# 06_-_POWER.net
KiCad netlist of a schematic drawn in Altium Designer
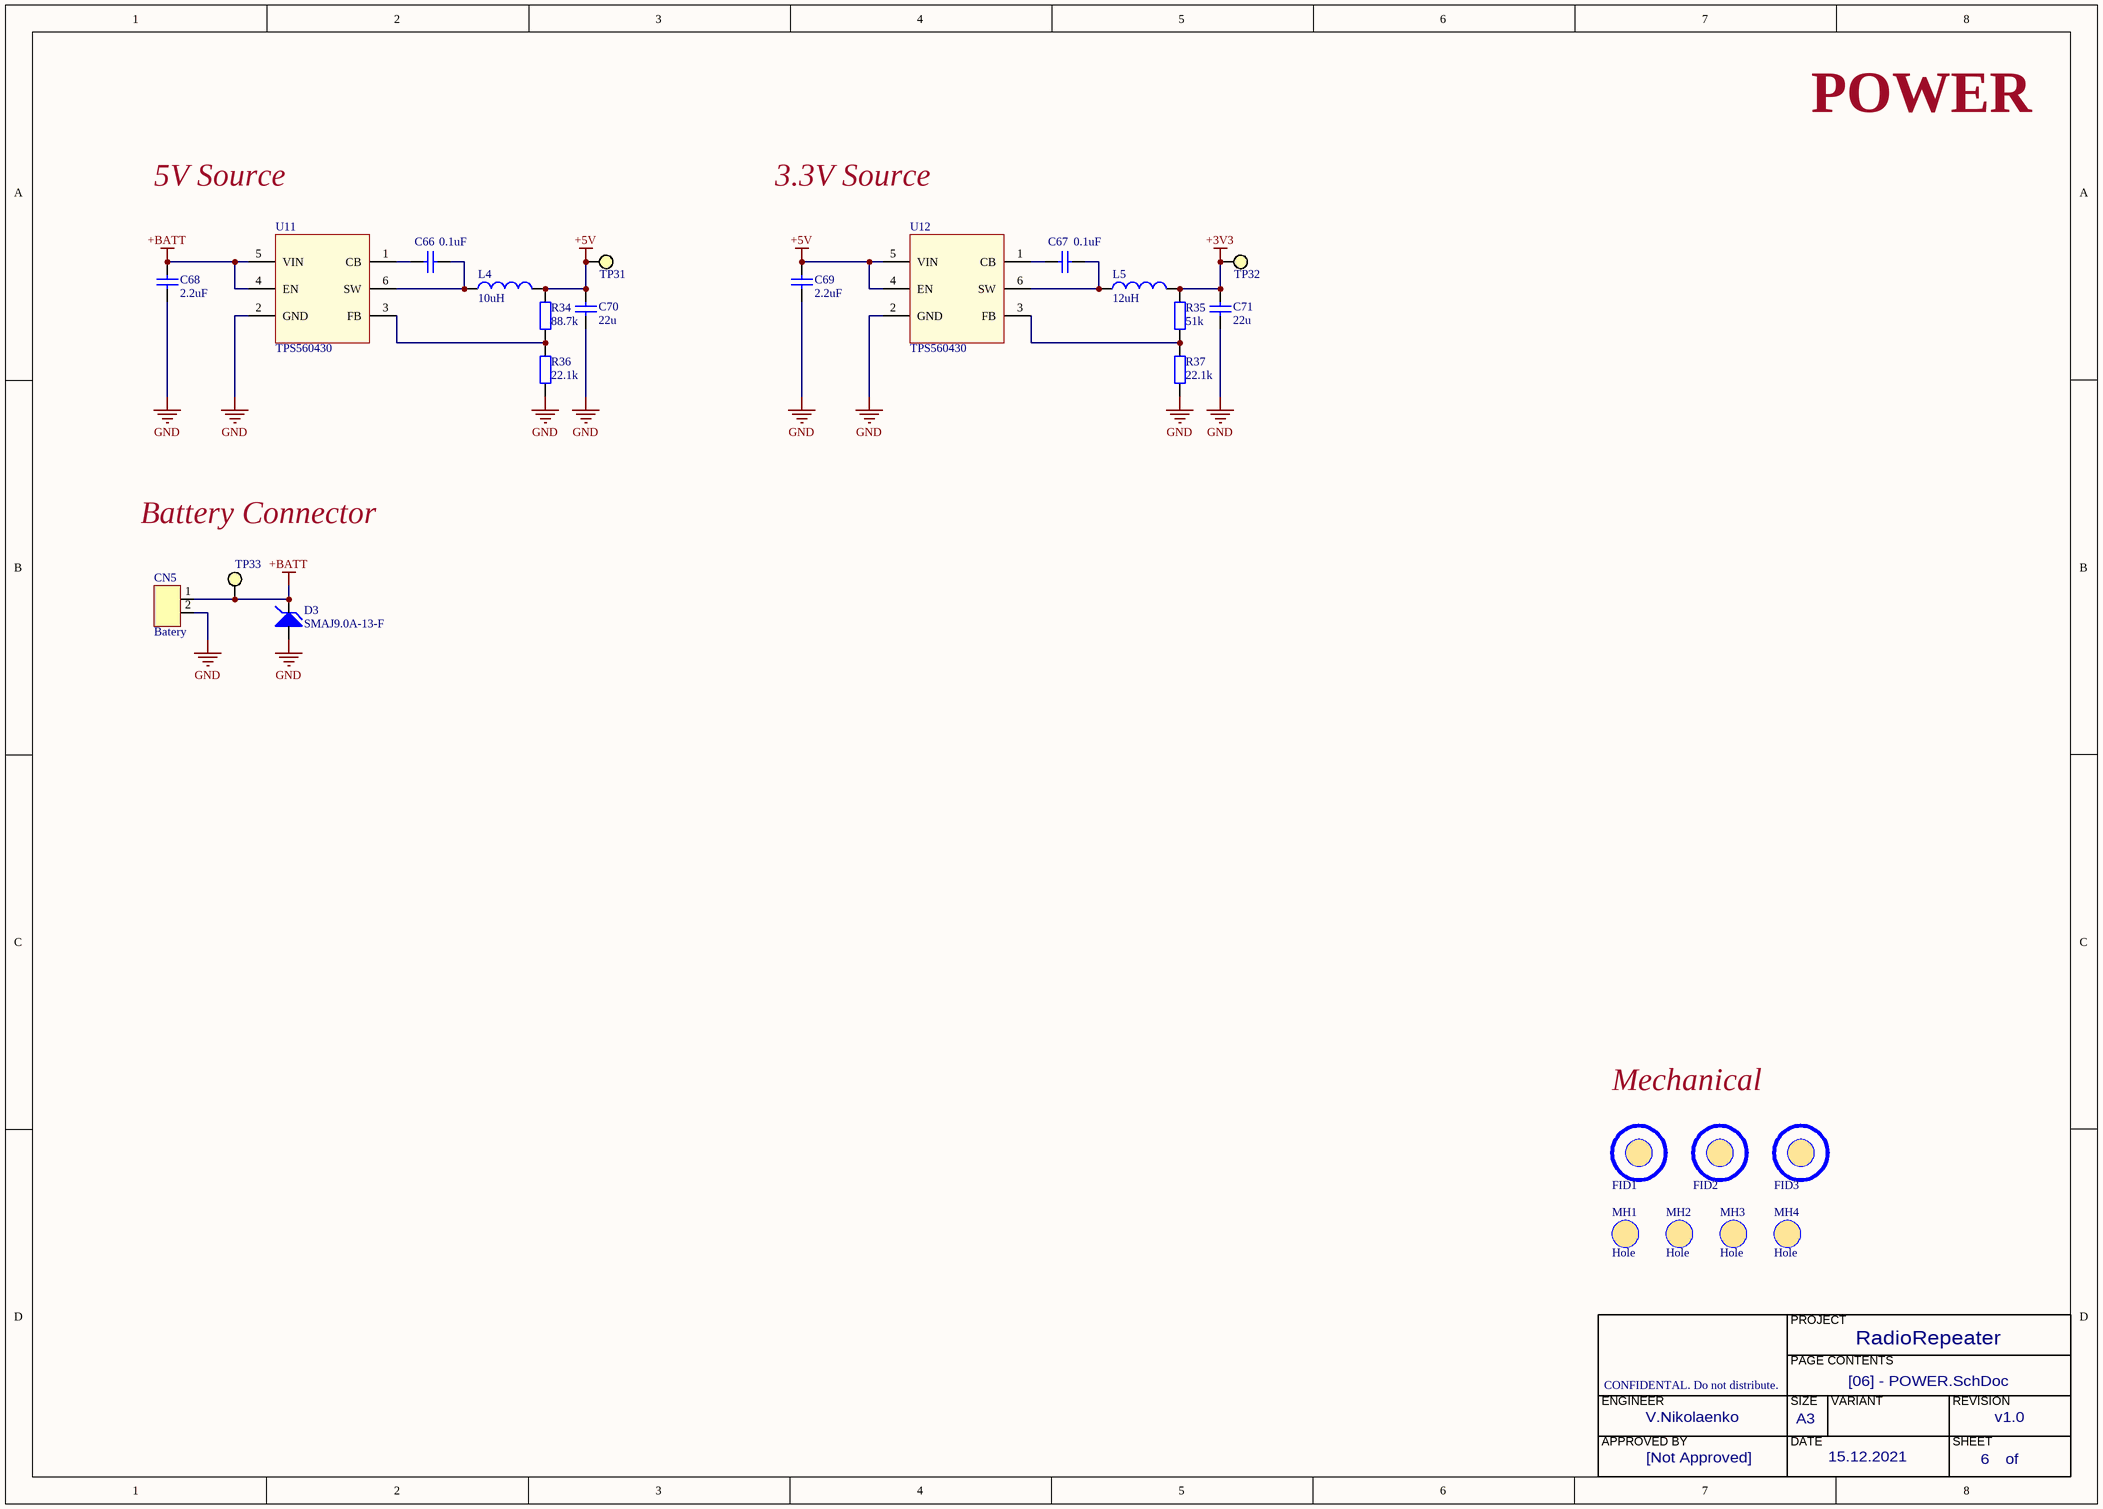
[diagram p0: [06] - POWER.SchDoc]

(export (version "E")
  (design (tool "Eeschema 10.0.6"))
  (components
    (comp (ref "C66")
      (value "0.1uF")
      (footprint "CAP0402")
      (description "Capacitor")
      (libsource (lib "PASSIVE&DISCRETE") (part "Cap"))
    )
    (comp (ref "C67")
      (value "0.1uF")
      (footprint "CAP0402")
      (description "Capacitor")
      (libsource (lib "PASSIVE&DISCRETE") (part "Cap"))
    )
    (comp (ref "C68")
      (value "2.2uF")
      (footprint "CAP0402")
      (description "Capacitor")
      (libsource (lib "PASSIVE&DISCRETE") (part "Cap"))
    )
    (comp (ref "C69")
      (value "2.2uF")
      (footprint "CAP0402")
      (description "Capacitor")
      (libsource (lib "PASSIVE&DISCRETE") (part "Cap"))
    )
    (comp (ref "C70")
      (value "22u")
      (footprint "CAP0402")
      (description "Capacitor")
      (libsource (lib "PASSIVE&DISCRETE") (part "Cap"))
    )
    (comp (ref "C71")
      (value "22u")
      (footprint "CAP0402")
      (description "Capacitor")
      (libsource (lib "PASSIVE&DISCRETE") (part "Cap"))
    )
    (comp (ref "CN5")
      (value "Batery")
      (footprint "H-D-1x2")
      (description "Connector 1x2")
      (libsource (lib "CONNECTORS") (part "CONN-1x2pin"))
    )
    (comp (ref "D3")
      (value "SMAJ9.0A-13-F")
      (footprint "SMB")
      (description "TVS DIODE")
      (libsource (lib "PASSIVE&DISCRETE") (part "Diode_TVS_Uni"))
    )
    (comp (ref "FID1")
      (value "Fiducial")
      (footprint "Fiducial")
      (libsource (lib "ELECTROMECHANICAL") (part "Fiducial"))
    )
    (comp (ref "FID2")
      (value "Fiducial")
      (footprint "Fiducial")
      (libsource (lib "ELECTROMECHANICAL") (part "Fiducial"))
    )
    (comp (ref "FID3")
      (value "Fiducial")
      (footprint "Fiducial")
      (libsource (lib "ELECTROMECHANICAL") (part "Fiducial"))
    )
    (comp (ref "L4")
      (value "10uH")
      (footprint "INDC0603-0201")
      (description "Inductor")
      (libsource (lib "PASSIVE&DISCRETE") (part "Inductor"))
    )
    (comp (ref "L5")
      (value "12uH")
      (footprint "INDC0603-0201")
      (description "Inductor")
      (libsource (lib "PASSIVE&DISCRETE") (part "Inductor"))
    )
    (comp (ref "MH1") (value "Hole") (libsource (lib "ELECTROMECHANICAL") (part "Hole")))
    (comp (ref "MH2") (value "Hole") (libsource (lib "ELECTROMECHANICAL") (part "Hole")))
    (comp (ref "MH3") (value "Hole") (libsource (lib "ELECTROMECHANICAL") (part "Hole")))
    (comp (ref "MH4") (value "Hole") (libsource (lib "ELECTROMECHANICAL") (part "Hole")))
    (comp (ref "R34")
      (value "88.7k")
      (footprint "RES0402")
      (description "Resistor")
      (libsource (lib "PASSIVE&DISCRETE") (part "Res"))
    )
    (comp (ref "R35")
      (value "51k")
      (footprint "RES0402")
      (description "Resistor")
      (libsource (lib "PASSIVE&DISCRETE") (part "Res"))
    )
    (comp (ref "R36")
      (value "22.1k")
      (footprint "RES0402")
      (description "Resistor")
      (libsource (lib "") (part "Res_1"))
    )
    (comp (ref "R37")
      (value "22.1k")
      (footprint "RES0402")
      (description "Resistor")
      (libsource (lib "") (part "Res_1"))
    )
    (comp (ref "TP31")
      (value "TestPoint")
      (footprint "TestPoint")
      (libsource (lib "CONNECTORS") (part "TestPoint"))
    )
    (comp (ref "TP32")
      (value "TestPoint")
      (footprint "TestPoint")
      (libsource (lib "CONNECTORS") (part "TestPoint"))
    )
    (comp (ref "TP33")
      (value "TestPoint")
      (footprint "TestPoint")
      (libsource (lib "CONNECTORS") (part "TestPoint"))
    )
    (comp (ref "U11")
      (value "TPS560430")
      (libsource (lib "Wheeled Robot Control Unit Library") (part "TPS560430"))
    )
    (comp (ref "U12")
      (value "TPS560430")
      (libsource (lib "Wheeled Robot Control Unit Library") (part "TPS560430"))
    )
  )
  (nets
    (net (code "1") (name "+3V3") (class "Default")
      (node (ref "C71") (pin "1") (pinfunction "1_1") (pintype "passive"))
      (node (ref "L5") (pin "2") (pinfunction "2_2") (pintype "passive"))
      (node (ref "R35") (pin "1") (pinfunction "1_1") (pintype "passive"))
      (node (ref "TP32") (pin "1") (pinfunction "1_1") (pintype "passive"))
    )
    (net (code "2") (name "+5V") (class "Default")
      (node (ref "C69") (pin "2") (pinfunction "2_2") (pintype "passive"))
      (node (ref "C70") (pin "1") (pinfunction "1_1") (pintype "passive"))
      (node (ref "L4") (pin "2") (pinfunction "2_2") (pintype "passive"))
      (node (ref "R34") (pin "1") (pinfunction "1_1") (pintype "passive"))
      (node (ref "TP31") (pin "1") (pinfunction "1_1") (pintype "passive"))
      (node (ref "U12") (pin "4") (pinfunction "EN_4") (pintype "passive"))
      (node (ref "U12") (pin "5") (pinfunction "VIN_5") (pintype "passive"))
    )
    (net (code "3") (name "+BATT") (class "Default")
      (node (ref "C68") (pin "2") (pinfunction "2_2") (pintype "passive"))
      (node (ref "CN5") (pin "1") (pinfunction "1_1") (pintype "passive"))
      (node (ref "D3") (pin "C") (pinfunction "C_C") (pintype "passive"))
      (node (ref "TP33") (pin "1") (pinfunction "1_1") (pintype "passive"))
      (node (ref "U11") (pin "4") (pinfunction "EN_4") (pintype "passive"))
      (node (ref "U11") (pin "5") (pinfunction "VIN_5") (pintype "passive"))
    )
    (net (code "4") (name "GND") (class "Default")
      (node (ref "C68") (pin "1") (pinfunction "1_1") (pintype "passive"))
      (node (ref "C69") (pin "1") (pinfunction "1_1") (pintype "passive"))
      (node (ref "C70") (pin "2") (pinfunction "2_2") (pintype "passive"))
      (node (ref "C71") (pin "2") (pinfunction "2_2") (pintype "passive"))
      (node (ref "CN5") (pin "2") (pinfunction "2_2") (pintype "passive"))
      (node (ref "D3") (pin "A") (pinfunction "A_A") (pintype "passive"))
      (node (ref "R36") (pin "1") (pinfunction "1_1") (pintype "passive"))
      (node (ref "R37") (pin "1") (pinfunction "1_1") (pintype "passive"))
      (node (ref "U11") (pin "2") (pinfunction "GND_2") (pintype "passive"))
      (node (ref "U12") (pin "2") (pinfunction "GND_2") (pintype "passive"))
    )
    (net (code "5") (name "Net-(U11-CB)") (class "Default")
      (node (ref "C66") (pin "2") (pinfunction "2_2") (pintype "passive"))
      (node (ref "U11") (pin "1") (pinfunction "CB_1") (pintype "passive"))
    )
    (net (code "6") (name "Net-(U11-FB)") (class "Default")
      (node (ref "R34") (pin "2") (pinfunction "2_2") (pintype "passive"))
      (node (ref "R36") (pin "2") (pinfunction "2_2") (pintype "passive"))
      (node (ref "U11") (pin "3") (pinfunction "FB_3") (pintype "passive"))
    )
    (net (code "7") (name "Net-(U11-SW)") (class "Default")
      (node (ref "C66") (pin "1") (pinfunction "1_1") (pintype "passive"))
      (node (ref "L4") (pin "1") (pinfunction "1_1") (pintype "passive"))
      (node (ref "U11") (pin "6") (pinfunction "SW_6") (pintype "passive"))
    )
    (net (code "8") (name "Net-(U12-CB)") (class "Default")
      (node (ref "C67") (pin "2") (pinfunction "2_2") (pintype "passive"))
      (node (ref "U12") (pin "1") (pinfunction "CB_1") (pintype "passive"))
    )
    (net (code "9") (name "Net-(U12-FB)") (class "Default")
      (node (ref "R35") (pin "2") (pinfunction "2_2") (pintype "passive"))
      (node (ref "R37") (pin "2") (pinfunction "2_2") (pintype "passive"))
      (node (ref "U12") (pin "3") (pinfunction "FB_3") (pintype "passive"))
    )
    (net (code "10") (name "Net-(U12-SW)") (class "Default")
      (node (ref "C67") (pin "1") (pinfunction "1_1") (pintype "passive"))
      (node (ref "L5") (pin "1") (pinfunction "1_1") (pintype "passive"))
      (node (ref "U12") (pin "6") (pinfunction "SW_6") (pintype "passive"))
    )
  )
)
